# AL5_Signal_Isolation.net
KiCad netlist of a schematic drawn in Altium Designer
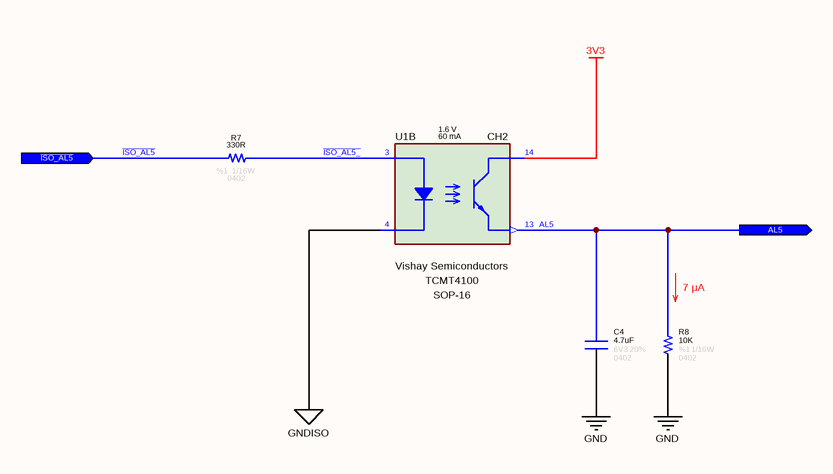
[diagram p0: AL5 Signal Isolation.SchDoc]

(export (version "E")
  (design (tool "Eeschema 10.0.6"))
  (components
    (comp (ref "C4")
      (value "4.7uF")
      (footprint "CAPACITOR_0402")
      (description "Multilayer Ceramic Capacitors - SMD - 6V3 4.7uF X5R 0402 20%")
      (fields
        (field (name "MANUFACTURER PART NUMBER") "C0402C475M9PACTU")
        (field (name "TOLERANCE") "20%")
        (field (name "CASE") "0402")
        (field (name "VOLTAGE") "6V3")
        (field (name "Comment") "Capacitor - 4.7uF [0402] (Ceramic)")
      )
      (libsource (lib "Akkoyun") (part "Capacitor - 4.7uF [0402-6V3]"))
    )
    (comp (ref "R7")
      (value "330R")
      (footprint "RESISTOR_0402")
      (description "Thick Film Resistors - SMD 1/16 W 330 Ohm 1%")
      (fields
        (field (name "MANUFACTURER PART NUMBER") "CRCW0402330RFKED")
        (field (name "CASE") "0402")
        (field (name "TOLERANCE") "%1")
        (field (name "POWER") "1/16W")
        (field (name "Comment") "330R - 0402 - %1 - 1/16W")
      )
      (libsource (lib "Akkoyun") (part "Resistor - 330R [0402]"))
    )
    (comp (ref "R8")
      (value "10K")
      (footprint "RESISTOR_0402")
      (description "Thick Film Resistors - SMD 1/16 W 10 KOhm 1%")
      (fields
        (field (name "MANUFACTURER PART NUMBER") "CRCW040210K0FKED")
        (field (name "TOLERANCE") "%1")
        (field (name "CASE") "0402")
        (field (name "POWER") "1/16W")
        (field (name "Comment") "10K - 0402 - %1 - 1/16W")
      )
      (libsource (lib "Akkoyun") (part "Resistor - 10K [0402]"))
    )
    (comp (ref "U1")
      (value "TCMT4100")
      (footprint "SO-16")
      (description "OptpCoupler 4CH 16 Pin (SOP16)")
      (fields
        (field (name "IF - FORWARD CURRENT") "60 mA")
        (field (name "VF - FORWARD VOLTAGE") "1.6 V")
        (field (name "MANUFACTURER NAME") "Vishay Semiconductors")
        (field (name "MANUFACTURER PART NUMBER") "TCMT4100")
        (field (name "CASE") "SOP-16")
      )
      (libsource (lib "Akkoyun") (part "IC - TCMT4100"))
    )
  )
  (nets
    (net (code "1") (name "/AL5") (class "Default")
      (node (ref "C4") (pin "2") (pinfunction "2_2") (pintype "passive"))
      (node (ref "R8") (pin "2") (pinfunction "2_2") (pintype "passive"))
      (node (ref "U1") (pin "13") (pinfunction "Emiter_CH2_13") (pintype "output"))
    )
    (net (code "2") (name "/~{ISO_AL5_}") (class "Default")
      (node (ref "R7") (pin "1") (pinfunction "1_1") (pintype "passive"))
      (node (ref "U1") (pin "3") (pinfunction "Anode_CH2_3") (pintype "passive"))
    )
    (net (code "3") (name "/~{ISO_AL5}") (class "Default")
      (node (ref "R7") (pin "2") (pinfunction "2_2") (pintype "passive"))
    )
    (net (code "4") (name "3V3") (class "Default")
      (node (ref "U1") (pin "14") (pinfunction "Collector_CH2_14") (pintype "passive"))
    )
    (net (code "5") (name "GND") (class "Default")
      (node (ref "C4") (pin "1") (pinfunction "1_1") (pintype "passive"))
      (node (ref "R8") (pin "1") (pinfunction "1_1") (pintype "passive"))
    )
    (net (code "6") (name "GNDISO") (class "Default")
      (node (ref "U1") (pin "4") (pinfunction "Cathode_CH2_4") (pintype "passive"))
    )
  )
)
